# BSPDSchematic.net
KiCad netlist of a schematic drawn in Altium Designer
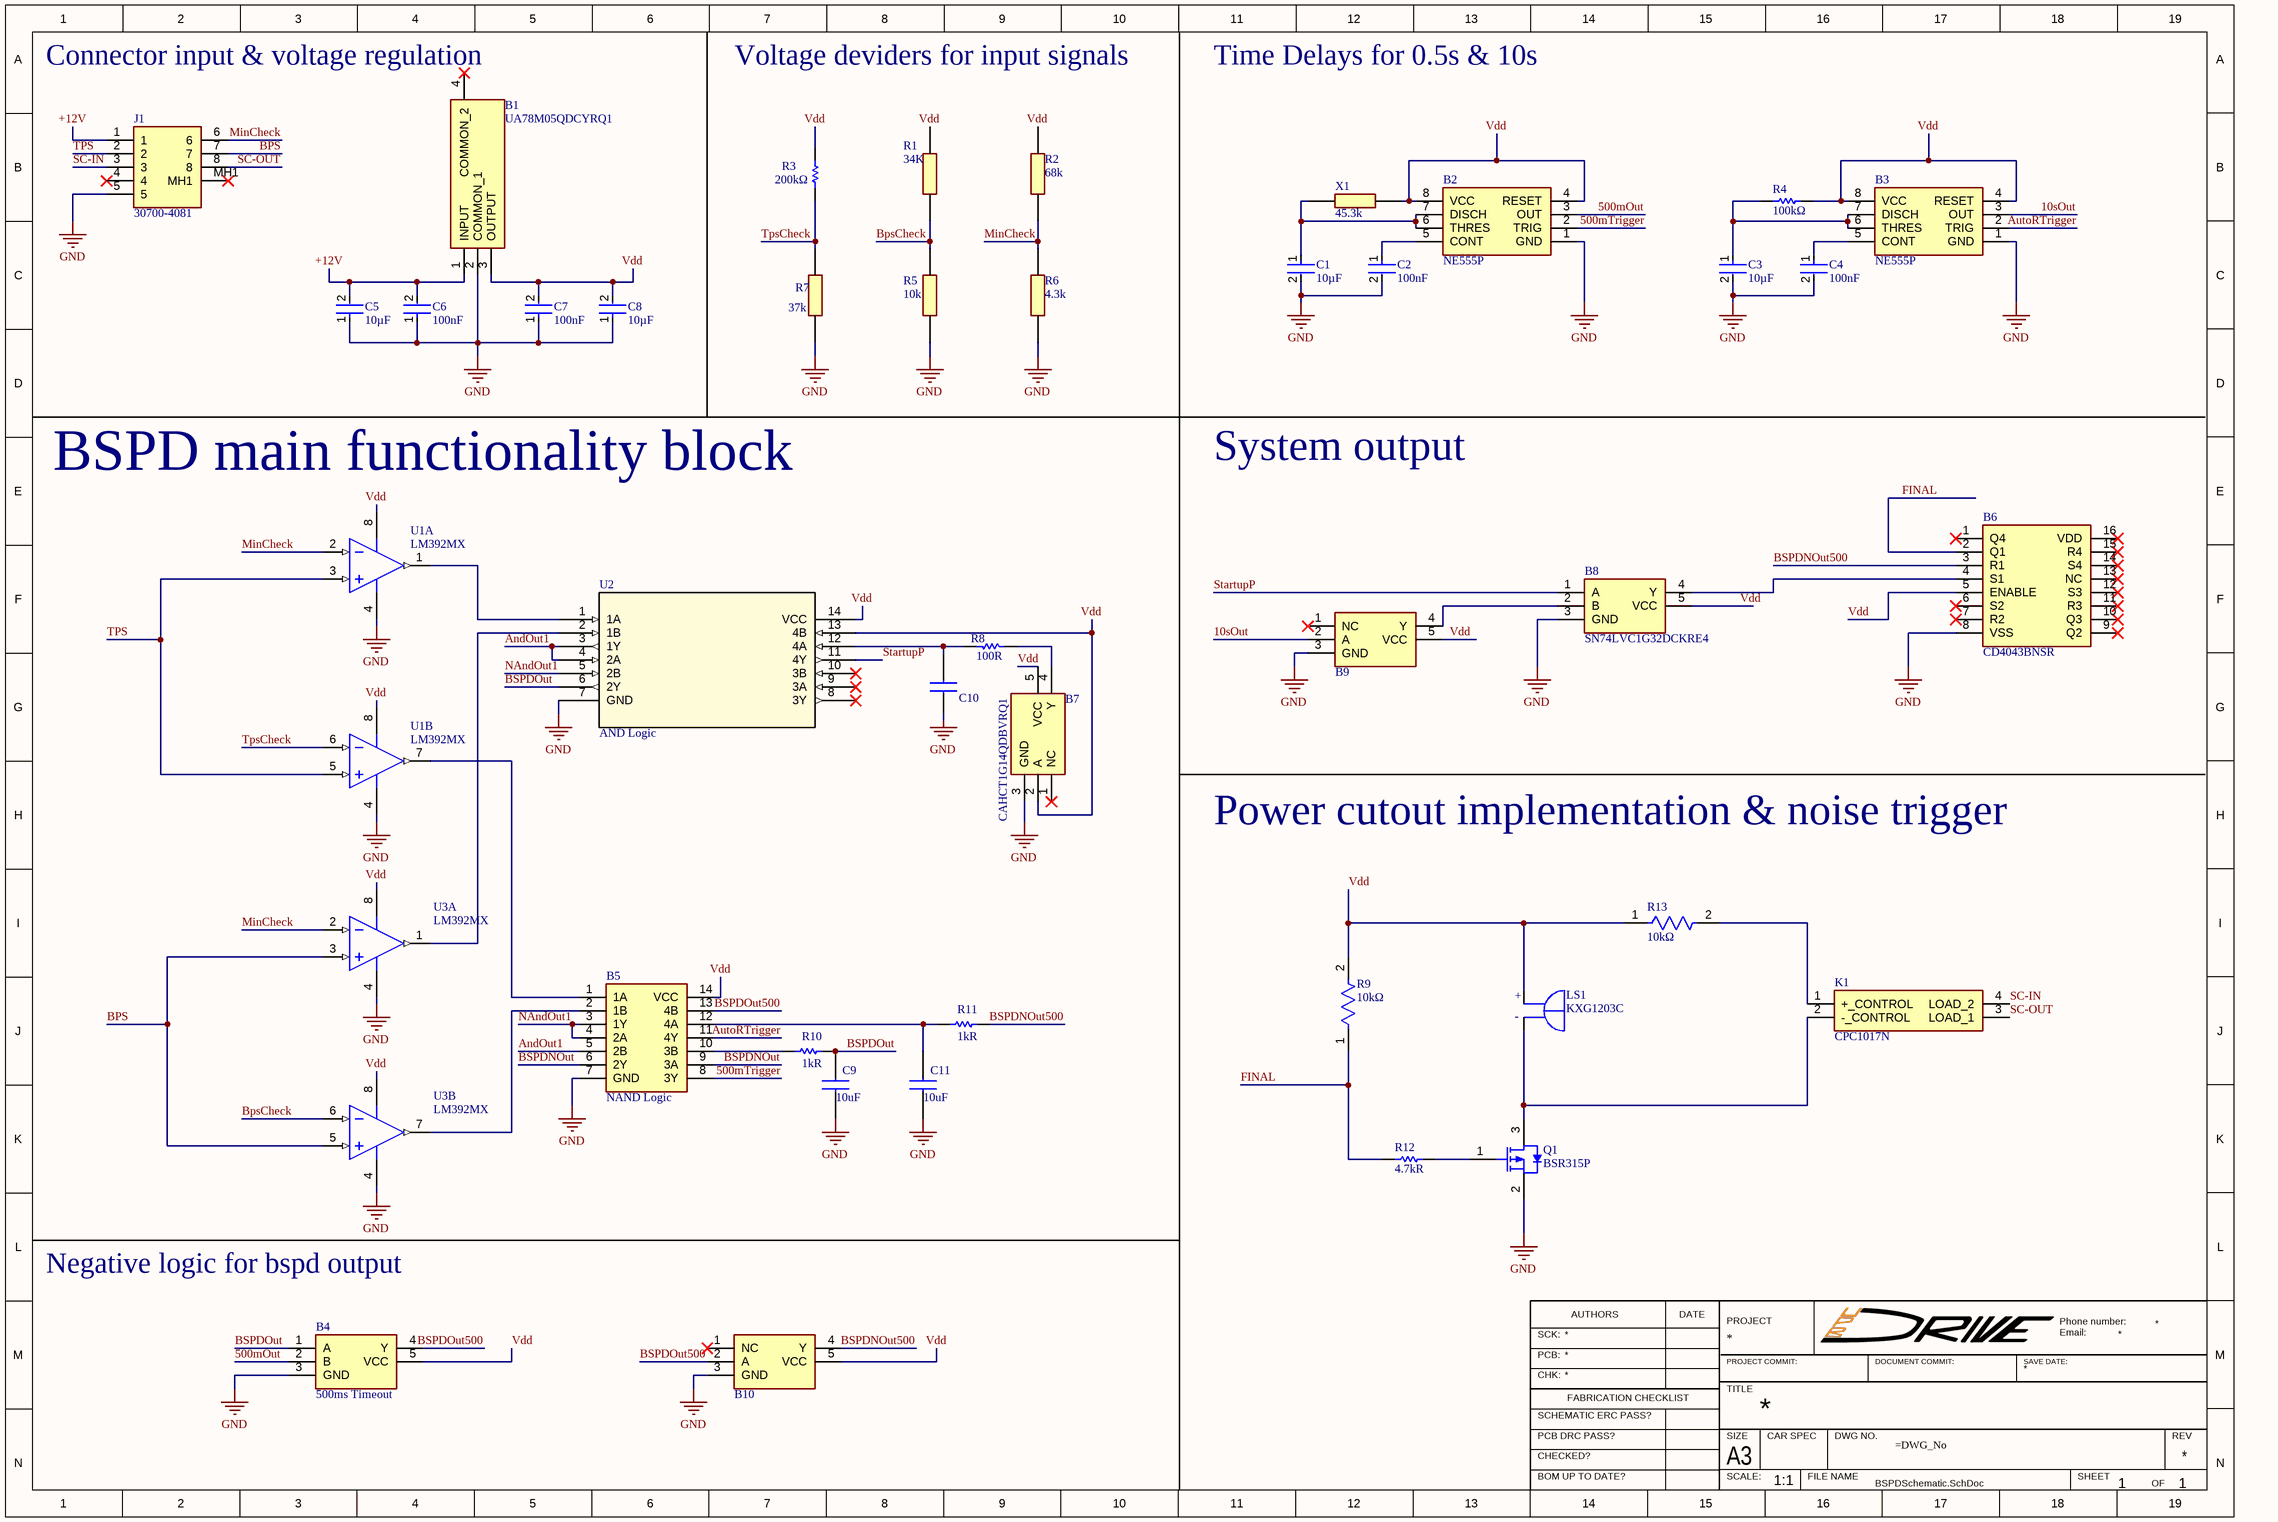
[diagram p0: BSPDSchematic.SchDoc]

(export (version "E")
  (design (tool "Eeschema 10.0.6"))
  (components
    (comp (ref "B1")
      (value "UA78M05QDCYRQ1")
      (footprint "SOT230P700X180-4N")
      (description "Standard Regulator Pos 5V 0.5A Automotive 4-Pin(3+Tab) SOT-223 T/R")
      (fields (field (name "MOUSER PART NUMBER") "595-UA78M05QDCYRQ1"))
      (libsource (lib "EMEA - Politehnica University of Bucharest - UPB Drive Formula Student Team") (part "UA78M05QDCYRQ1"))
    )
    (comp (ref "B2")
      (value "NE555P")
      (footprint "DIP794W53P254L959H508Q8N")
      (fields (field (name "MOUSER PART NUMBER") "595-NE555P"))
      (libsource (lib "EMEA - Politehnica University of Bucharest - UPB Drive Formula Student Team") (part "NE555P"))
    )
    (comp (ref "B3")
      (value "NE555P")
      (footprint "DIP794W53P254L959H508Q8N")
      (fields (field (name "MOUSER PART NUMBER") "595-NE555P"))
      (libsource (lib "EMEA - Politehnica University of Bucharest - UPB Drive Formula Student Team") (part "NE555P"))
    )
    (comp (ref "B4")
      (value "500ms Timeout")
      (footprint "SOT65P210X110-5N")
      (description "IC GATE XOR 1CH 2-INP SC70-5")
      (fields
        (field (name "MOUSER PART NUMBER") "595-SN74AHC1G86DCKE4")
        (field (name "MANUFACTURER_PART_NUMBER") "SN74AHC1G86DCKRE4")
      )
      (libsource (lib "EMEA - Politehnica University of Bucharest - UPB Drive Formula Student Team") (part "SN74AHC1G86DCKRE4"))
    )
    (comp (ref "B5")
      (value "NAND Logic")
      (footprint "SOIC127P780X200-14N")
      (description "Quadruple 2-Input Positive-NAND Gates")
      (fields
        (field (name "MANUFACTURER_PART_NUMBER") "SN74ACT00NSR")
        (field (name "MOUSER PART NUMBER") "595-SN74ACT00NSR")
      )
      (libsource (lib "EMEA - Politehnica University of Bucharest - UPB Drive Formula Student Team") (part "SN74ACT00NSR"))
    )
    (comp (ref "B6")
      (value "CD4043BNSR")
      (footprint "SOIC127P780X200-16N")
      (description "CMOS Quad NOR R/S Latch with 3-State Outputs")
      (fields (field (name "MOUSER PART NUMBER") "595-CD4043BNSR"))
      (libsource (lib "EMEA - Politehnica University of Bucharest - UPB Drive Formula Student Team") (part "CD4043BNSR"))
    )
    (comp (ref "B7")
      (value "CAHCT1G14QDBVRQ1")
      (footprint "SOT95P280X145-5N")
      (description "Automotive single 4.5V-to-5.5V inverter with Schmitt-trigger inputs")
      (fields (field (name "MOUSER PART NUMBER") "595-CAHCT1G14QDBVRQ1"))
      (libsource (lib "EMEA - Politehnica University of Bucharest - UPB Drive Formula Student Team") (part "CAHCT1G14QDBVRQ1"))
    )
    (comp (ref "B8")
      (value "SN74LVC1G32DCKRE4")
      (footprint "SOT65P210X110-5N")
      (description "OR Gate 1-Element 2-IN CMOS 5-Pin SC-70 T/R")
      (fields (field (name "MOUSER PART NUMBER") "595-74LVC1G32DCKRE4"))
      (libsource (lib "EMEA - Politehnica University of Bucharest - UPB Drive Formula Student Team") (part "SN74LVC1G32DCKRE4"))
    )
    (comp (ref "B9")
      (value "CAHCT1G14QDBVRQ1")
      (footprint "SOT95P280X145-5N")
      (description "Automotive single 4.5V-to-5.5V inverter with Schmitt-trigger inputs")
      (fields (field (name "MOUSER PART NUMBER") "595-CAHCT1G14QDBVRQ1"))
      (libsource (lib "EMEA - Politehnica University of Bucharest - UPB Drive Formula Student Team") (part "CAHCT1G14QDBVRQ1"))
    )
    (comp (ref "B10")
      (value "CAHCT1G14QDBVRQ1")
      (footprint "SOT95P280X145-5N")
      (description "Automotive single 4.5V-to-5.5V inverter with Schmitt-trigger inputs")
      (fields (field (name "MOUSER PART NUMBER") "595-CAHCT1G14QDBVRQ1"))
      (libsource (lib "EMEA - Politehnica University of Bucharest - UPB Drive Formula Student Team") (part "CAHCT1G14QDBVRQ1"))
    )
    (comp (ref "C1")
      (value "10µF")
      (footprint "FP-GRM21B-0_2-e0_2_0_7-MFG")
      (description "Multilayer Ceramic Capacitors MLCC - SMD/SMTSimulate & compare characteristics in SimSurfing")
      (fields (field (name "TOLERANCE") "20%") (field (name "Comment") "GRM21BR61H106ME43K"))
      (libsource (lib "EMEA - Politehnica University of Bucharest - UPB Drive Formula Student Team") (part "b4654b650e69147ec39a6b967a45e02"))
    )
    (comp (ref "C2")
      (value "100nF")
      (footprint "FP-CL31-IPC_C")
      (fields (field (name "Comment") "CL31B104KBCNNNL"))
      (libsource (lib "EMEA - Politehnica University of Bucharest - UPB Drive Formula Student Team") (part "b4654b650e69147ec39a6b967a45e02"))
    )
    (comp (ref "C3")
      (value "10µF")
      (footprint "FP-GRM21B-0_2-e0_2_0_7-MFG")
      (description "Multilayer Ceramic Capacitors MLCC - SMD/SMTSimulate & compare characteristics in SimSurfing")
      (fields (field (name "TOLERANCE") "20%") (field (name "Comment") "GRM21BR61H106ME43K"))
      (libsource (lib "EMEA - Politehnica University of Bucharest - UPB Drive Formula Student Team") (part "b4654b650e69147ec39a6b967a45e02"))
    )
    (comp (ref "C4")
      (value "100nF")
      (footprint "FP-CL31-IPC_C")
      (fields (field (name "Comment") "CL31B104KBCNNNL"))
      (libsource (lib "EMEA - Politehnica University of Bucharest - UPB Drive Formula Student Team") (part "b4654b650e69147ec39a6b967a45e02"))
    )
    (comp (ref "C5")
      (value "10µF")
      (footprint "FP-GRM21B-0_2-e0_2_0_7-MFG")
      (description "Multilayer Ceramic Capacitors MLCC - SMD/SMTSimulate & compare characteristics in SimSurfing")
      (fields (field (name "TOLERANCE") "20%") (field (name "Comment") "GRM21BR61H106ME43K"))
      (libsource (lib "EMEA - Politehnica University of Bucharest - UPB Drive Formula Student Team") (part "b4654b650e69147ec39a6b967a45e02"))
    )
    (comp (ref "C6")
      (value "100nF")
      (footprint "FP-0805-L_2_01_0_2-W_1_25-IPC_B")
      (fields (field (name "Comment") "08051C104K4Z2A"))
      (libsource (lib "EMEA - Politehnica University of Bucharest - UPB Drive Formula Student Team") (part "b4654b650e69147ec39a6b967a45e02"))
    )
    (comp (ref "C7")
      (value "100nF")
      (footprint "FP-0805-L_2_01_0_2-W_1_25-IPC_B")
      (fields (field (name "Comment") "08051C104K4Z2A"))
      (libsource (lib "EMEA - Politehnica University of Bucharest - UPB Drive Formula Student Team") (part "b4654b650e69147ec39a6b967a45e02"))
    )
    (comp (ref "C8")
      (value "10µF")
      (footprint "FP-GRM21B-0_2-e0_2_0_7-MFG")
      (description "Multilayer Ceramic Capacitors MLCC - SMD/SMTSimulate & compare characteristics in SimSurfing")
      (fields (field (name "TOLERANCE") "20%") (field (name "Comment") "GRM21BR61H106ME43K"))
      (libsource (lib "EMEA - Politehnica University of Bucharest - UPB Drive Formula Student Team") (part "b4654b650e69147ec39a6b967a45e02"))
    )
    (comp (ref "C9")
      (value "10uF")
      (footprint "GRM21BR60J226ME39L")
      (description "Multilayer Ceramic Capacitors MLCC - SMD/SMT 0805 10uF 20volts *Derate Voltage/Temp")
      (fields
        (field (name "MANUFACTURER_PART_NUMBER") "GRM21BC81D106KE51K")
        (field (name "MOUSER PART NUMBER") "81-GRM21BC81D106KE1K")
      )
      (libsource (lib "EMEA - Politehnica University of Bucharest - UPB Drive Formula Student Team") (part "GRM21BC81D106KE51K"))
    )
    (comp (ref "C10")
      (value "CL31A107MQHNNWE")
      (footprint "CAPC3216X180N")
      (fields (field (name "MOUSER PART NUMBER") "187-CL31A107MQHNNWE"))
      (libsource (lib "EMEA - Politehnica University of Bucharest - UPB Drive Formula Student Team") (part "CL31A107MQHNNWE"))
    )
    (comp (ref "C11")
      (value "10uF")
      (footprint "GRM21BR60J226ME39L")
      (description "Multilayer Ceramic Capacitors MLCC - SMD/SMT 0805 10uF 20volts *Derate Voltage/Temp")
      (fields
        (field (name "MANUFACTURER_PART_NUMBER") "GRM21BC81D106KE51K")
        (field (name "MOUSER PART NUMBER") "81-GRM21BC81D106KE1K")
      )
      (libsource (lib "EMEA - Politehnica University of Bucharest - UPB Drive Formula Student Team") (part "GRM21BC81D106KE51K"))
    )
    (comp (ref "J1")
      (value "30700-4081")
      (footprint "307004081")
      (description "Automotive Connectors HDAC64 DR VERT HDR 8 DR 8 CKT BLACK POL 2")
      (fields (field (name "MOUSER PART NUMBER") "538-30700-4081"))
      (libsource (lib "EMEA - Politehnica University of Bucharest - UPB Drive Formula Student Team") (part "30700-4081"))
    )
    (comp (ref "K1")
      (value "CPC1017N")
      (footprint "SOP254P610X206-4N")
      (description "Relay SSR 50mA 1.4V DC-IN 0.1A 60V 4-Pin SOP Tube")
      (fields (field (name "MOUSER PART NUMBER") "849-CPC1017N"))
      (libsource (lib "EMEA - Politehnica University of Bucharest - UPB Drive Formula Student Team") (part "CPC1017N"))
    )
    (comp (ref "LS1")
      (value "KXG1203C")
      (footprint "XDCR_KXG1203C")
      (libsource (lib "EMEA - Politehnica University of Bucharest - UPB Drive Formula Student Team") (part "KXG1203C"))
    )
    (comp (ref "Q1")
      (value "BSR315P")
      (footprint "INF-PG-SC59_M")
      (libsource (lib "EMEA - Politehnica University of Bucharest - UPB Drive Formula Student Team") (part "INF-PEMOS-GSD-3"))
    )
    (comp (ref "R1")
      (value "34K")
      (footprint "MCS04020C1003FE000")
      (description "Vishay Resistor Chip 0402")
      (fields (field (name "MANUFACTURER_PART_NUMBER") "MCS04020D3402BE000"))
      (libsource (lib "EMEA - Politehnica University of Bucharest - UPB Drive Formula Student Team") (part "MCS04020D3402BE000"))
    )
    (comp (ref "R2")
      (value "68k")
      (footprint "RESC1608X55N")
      (description "Thin Film Resistors - SMD MCT 0603-15 0.1% AT P5 68K")
      (fields
        (field (name "MANUFACTURER_PART_NUMBER") "MCT0603ME6802BP500")
        (field (name "MOUSER PART NUMBER") "594-MCT0603ME6802BP5")
      )
      (libsource (lib "EMEA - Politehnica University of Bucharest - UPB Drive Formula Student Team") (part "MCT0603ME6802BP500"))
    )
    (comp (ref "R3")
      (value "200kΩ")
      (footprint "RESC2013X60X35ML10T20")
      (description "Res Thick Film 0805 200K Ohm 1% 0.125W(1/8W) ±100ppm/C Molded SMD T/R")
      (fields (field (name "TOLERANCE") "1%") (field (name "Comment") "RC0805FR-13200KL"))
      (libsource (lib "EMEA - Politehnica University of Bucharest - UPB Drive Formula Student Team") (part "RES"))
    )
    (comp (ref "R4")
      (value "100kΩ")
      (footprint "RESC2013X60X30ML20T20")
      (description "Resistor Thick Film 0805 100K Ohm 1% 1/8W ±100ppm/°C SMD Punched Paper Tape and Reel")
      (fields (field (name "TOLERANCE") "1%") (field (name "Comment") "RK73H2ATTD1003F"))
      (libsource (lib "EMEA - Politehnica University of Bucharest - UPB Drive Formula Student Team") (part "RES"))
    )
    (comp (ref "R5")
      (value "10k")
      (footprint "RESC6332X70N")
      (description "10 +/-5% 1W Chip Resistor 2512 (6432 Metric) Automotive AEC-Q200 Thick Film")
      (fields
        (field (name "MOUSER PART NUMBER") "652-CR2512AJW-103ELF")
        (field (name "MANUFACTURER_PART_NUMBER") "CR2512AJW-103ELF")
      )
      (libsource (lib "EMEA - Politehnica University of Bucharest - UPB Drive Formula Student Team") (part "CR2512AJW-103ELF"))
    )
    (comp (ref "R6")
      (value "4.3k")
      (footprint "RESC1608X50N")
      (description "Thick Film Resistors - SMD 1/10watt 4.3Kohms 1%")
      (fields
        (field (name "MANUFACTURER_PART_NUMBER") "CRCW06034K30FKTA")
        (field (name "MOUSER PART NUMBER") "71-CRCW0603-4.3K")
      )
      (libsource (lib "EMEA - Politehnica University of Bucharest - UPB Drive Formula Student Team") (part "CRCW06034K30FKTA"))
    )
    (comp (ref "R7")
      (value "37k")
      (footprint "RESC1608X55N")
      (description "Lead (Pb)-Bearing High Stability Thin Film Chip Resistors")
      (fields
        (field (name "MOUSER PART NUMBER") "71-TNPW060337K0BEEA")
        (field (name "MANUFACTURER_PART_NUMBER") "TNPW060337K0BEEA")
      )
      (libsource (lib "EMEA - Politehnica University of Bucharest - UPB Drive Formula Student Team") (part "TNPW060337K0BEEA"))
    )
    (comp (ref "R8")
      (value "100R")
      (footprint "RESC3116X65X40ML10T20")
      (fields
        (field (name "TOLERANCE") "1%")
        (field (name "POWER") "250mW")
        (field (name "Comment") "RC1206FR-07100RL")
      )
      (libsource (lib "EMEA - Politehnica University of Bucharest - UPB Drive Formula Student Team") (part "RES-2"))
    )
    (comp (ref "R9")
      (value "10kΩ")
      (footprint "FP-RN731J-IPC_B")
      (description "RN 0603 SMD precision chip resistor 10K")
      (fields (field (name "TOLERANCE") "0.1%") (field (name "Comment") "RN73C1J10KB"))
      (libsource (lib "EMEA - Politehnica University of Bucharest - UPB Drive Formula Student Team") (part "1029c3af85768c4190bb7ad29bc67b5"))
    )
    (comp (ref "R10")
      (value "1kR")
      (footprint "RESC3216X60X45LL15T20")
      (fields
        (field (name "TOLERANCE") "1%")
        (field (name "POWER") "250mW")
        (field (name "Comment") "CRCW12061K00FKEA")
      )
      (libsource (lib "EMEA - Politehnica University of Bucharest - UPB Drive Formula Student Team") (part "RES-2"))
    )
    (comp (ref "R11")
      (value "1kR")
      (footprint "RESC3216X60X45LL15T20")
      (fields
        (field (name "TOLERANCE") "1%")
        (field (name "POWER") "250mW")
        (field (name "Comment") "CRCW12061K00FKEA")
      )
      (libsource (lib "EMEA - Politehnica University of Bucharest - UPB Drive Formula Student Team") (part "RES-2"))
    )
    (comp (ref "R12")
      (value "4.7kR")
      (footprint "RESC3216X60X45LL15T20")
      (fields
        (field (name "TOLERANCE") "1%")
        (field (name "POWER") "250mW")
        (field (name "Comment") "CRCW12064K70FKEA")
      )
      (libsource (lib "EMEA - Politehnica University of Bucharest - UPB Drive Formula Student Team") (part "RES-2"))
    )
    (comp (ref "R13")
      (value "10kΩ")
      (footprint "FP-RN731J-IPC_B")
      (description "RN 0603 SMD precision chip resistor 10K")
      (fields (field (name "TOLERANCE") "0.1%") (field (name "Comment") "RN73C1J10KB"))
      (libsource (lib "EMEA - Politehnica University of Bucharest - UPB Drive Formula Student Team") (part "1029c3af85768c4190bb7ad29bc67b5"))
    )
    (comp (ref "U1")
      (value "LM392MX")
      (footprint "D0008A_L")
      (description "lm392-N Low Power Operational Amplifier/Voltage Comparator")
      (libsource (lib "EMEA - Politehnica University of Bucharest - UPB Drive Formula Student Team") (part "AN-COMP-LM392-8"))
    )
    (comp (ref "U2")
      (value "AND Logic")
      (footprint "D14")
      (description "4-ch, 2-input, 2-V to 6-V 5.2 mA drive strength AND gate 14-SOIC -55 to 125")
      (fields
        (field (name "MANUFACTURER_PART_NUMBER") "CD74HC08M")
        (field (name "COPYRIGHT") "Copyright (C) 2025 Ultra Librarian. All rights reserved.")
      )
      (libsource (lib "EMEA - Politehnica University of Bucharest - UPB Drive Formula Student Team") (part "CD74HC08M"))
    )
    (comp (ref "U3")
      (value "LM392MX")
      (footprint "D0008A_L")
      (description "lm392-N Low Power Operational Amplifier/Voltage Comparator")
      (libsource (lib "EMEA - Politehnica University of Bucharest - UPB Drive Formula Student Team") (part "AN-COMP-LM392-8"))
    )
    (comp (ref "X1")
      (value "45.3k")
      (footprint "RESC3216X65N")
      (description "Thick Film Resistors - SMD 1206 45.3Kohm 1% High VoltageAEC-Q200")
      (fields
        (field (name "MANUFACTURER_PART_NUMBER") "KTR18EZPF4532")
        (field (name "MOUSER PART NUMBER") "755-KTR18EZPF4532")
      )
      (libsource (lib "EMEA - Politehnica University of Bucharest - UPB Drive Formula Student Team") (part "KTR18EZPF4532"))
    )
  )
  (nets
    (net (code "1") (name "/+12V") (class "Default")
      (node (ref "B1") (pin "1") (pinfunction "INPUT_1") (pintype "passive"))
      (node (ref "C5") (pin "2") (pinfunction "2_2") (pintype "passive"))
      (node (ref "C6") (pin "2") (pinfunction "2_2") (pintype "passive"))
      (node (ref "J1") (pin "1") (pinfunction "1_1") (pintype "passive"))
    )
    (net (code "2") (name "/10sOut") (class "Default")
      (node (ref "B3") (pin "3") (pinfunction "OUT_3") (pintype "passive"))
      (node (ref "B9") (pin "2") (pinfunction "A_2") (pintype "passive"))
    )
    (net (code "3") (name "/500mOut") (class "Default")
      (node (ref "B2") (pin "3") (pinfunction "OUT_3") (pintype "passive"))
      (node (ref "B4") (pin "2") (pinfunction "B_2") (pintype "passive"))
    )
    (net (code "4") (name "/500mTrigger") (class "Default")
      (node (ref "B2") (pin "2") (pinfunction "TRIG_2") (pintype "passive"))
      (node (ref "B5") (pin "8") (pinfunction "3Y_8") (pintype "passive"))
    )
    (net (code "5") (name "/AndOut1") (class "Default")
      (node (ref "B5") (pin "5") (pinfunction "2B_5") (pintype "passive"))
      (node (ref "U2") (pin "3") (pinfunction "1Y_3") (pintype "output"))
      (node (ref "U2") (pin "4") (pinfunction "2A_4") (pintype "input"))
    )
    (net (code "6") (name "/AutoRTrigger") (class "Default")
      (node (ref "B3") (pin "2") (pinfunction "TRIG_2") (pintype "passive"))
      (node (ref "B5") (pin "11") (pinfunction "4Y_11") (pintype "passive"))
    )
    (net (code "7") (name "/BPS") (class "Default")
      (node (ref "J1") (pin "7") (pinfunction "7_7") (pintype "passive"))
      (node (ref "U3") (pin "3") (pinfunction "INA+_3") (pintype "input"))
      (node (ref "U3") (pin "5") (pinfunction "INB+_5") (pintype "input"))
    )
    (net (code "8") (name "/BSPDNOut") (class "Default")
      (node (ref "B5") (pin "6") (pinfunction "2Y_6") (pintype "passive"))
      (node (ref "B5") (pin "9") (pinfunction "3A_9") (pintype "passive"))
    )
    (net (code "9") (name "/BSPDNOut500") (class "Default")
      (node (ref "B10") (pin "4") (pinfunction "Y_4") (pintype "passive"))
      (node (ref "B6") (pin "3") (pinfunction "R1_3") (pintype "passive"))
      (node (ref "R11") (pin "2") (pinfunction "2_2") (pintype "passive"))
    )
    (net (code "10") (name "/BSPDOut") (class "Default")
      (node (ref "B4") (pin "1") (pinfunction "A_1") (pintype "passive"))
      (node (ref "C9") (pin "2") (pinfunction "2_2") (pintype "passive"))
      (node (ref "R10") (pin "2") (pinfunction "2_2") (pintype "passive"))
      (node (ref "U2") (pin "6") (pinfunction "2Y_6") (pintype "output"))
    )
    (net (code "11") (name "/BSPDOut500") (class "Default")
      (node (ref "B10") (pin "2") (pinfunction "A_2") (pintype "passive"))
      (node (ref "B4") (pin "4") (pinfunction "Y_4") (pintype "passive"))
      (node (ref "B5") (pin "13") (pinfunction "4B_13") (pintype "passive"))
    )
    (net (code "12") (name "/BpsCheck") (class "Default")
      (node (ref "R1") (pin "1") (pinfunction "1_1") (pintype "passive"))
      (node (ref "R5") (pin "2") (pinfunction "2_2") (pintype "passive"))
      (node (ref "U3") (pin "6") (pinfunction "INB-_6") (pintype "input"))
    )
    (net (code "13") (name "/FINAL") (class "Default")
      (node (ref "B6") (pin "2") (pinfunction "Q1_2") (pintype "passive"))
      (node (ref "R12") (pin "1") (pinfunction "1_1") (pintype "passive"))
      (node (ref "R9") (pin "1") (pinfunction "1_1") (pintype "passive"))
    )
    (net (code "14") (name "/MinCheck") (class "Default")
      (node (ref "J1") (pin "6") (pinfunction "6_6") (pintype "passive"))
      (node (ref "R2") (pin "1") (pinfunction "1_1") (pintype "passive"))
      (node (ref "R6") (pin "2") (pinfunction "2_2") (pintype "passive"))
      (node (ref "U1") (pin "2") (pinfunction "INA-_2") (pintype "input"))
      (node (ref "U3") (pin "2") (pinfunction "INA-_2") (pintype "input"))
    )
    (net (code "15") (name "/NAndOut1") (class "Default")
      (node (ref "B5") (pin "3") (pinfunction "1Y_3") (pintype "passive"))
      (node (ref "B5") (pin "4") (pinfunction "2A_4") (pintype "passive"))
      (node (ref "U2") (pin "5") (pinfunction "2B_5") (pintype "input"))
    )
    (net (code "16") (name "/SC-IN") (class "Default")
      (node (ref "J1") (pin "3") (pinfunction "3_3") (pintype "passive"))
      (node (ref "K1") (pin "4") (pinfunction "LOAD_2_4") (pintype "passive"))
    )
    (net (code "17") (name "/SC-OUT") (class "Default")
      (node (ref "J1") (pin "8") (pinfunction "8_8") (pintype "passive"))
      (node (ref "K1") (pin "3") (pinfunction "LOAD_1_3") (pintype "passive"))
    )
    (net (code "18") (name "/StartupP") (class "Default")
      (node (ref "B8") (pin "1") (pinfunction "A_1") (pintype "passive"))
      (node (ref "U2") (pin "11") (pinfunction "4Y_11") (pintype "output"))
    )
    (net (code "19") (name "/TPS") (class "Default")
      (node (ref "J1") (pin "2") (pinfunction "2_2") (pintype "passive"))
      (node (ref "U1") (pin "3") (pinfunction "INA+_3") (pintype "input"))
      (node (ref "U1") (pin "5") (pinfunction "INB+_5") (pintype "input"))
    )
    (net (code "20") (name "/TpsCheck") (class "Default")
      (node (ref "R3") (pin "1") (pinfunction "1_1") (pintype "passive"))
      (node (ref "R7") (pin "2") (pinfunction "2_2") (pintype "passive"))
      (node (ref "U1") (pin "6") (pinfunction "INB-_6") (pintype "input"))
    )
    (net (code "21") (name "/Vdd") (class "Default")
      (node (ref "B1") (pin "3") (pinfunction "OUTPUT_3") (pintype "passive"))
      (node (ref "B10") (pin "5") (pinfunction "VCC_5") (pintype "passive"))
      (node (ref "B2") (pin "4") (pinfunction "RESET_4") (pintype "passive"))
      (node (ref "B2") (pin "8") (pinfunction "VCC_8") (pintype "passive"))
      (node (ref "B3") (pin "4") (pinfunction "RESET_4") (pintype "passive"))
      (node (ref "B3") (pin "8") (pinfunction "VCC_8") (pintype "passive"))
      (node (ref "B4") (pin "5") (pinfunction "VCC_5") (pintype "passive"))
      (node (ref "B5") (pin "14") (pinfunction "VCC_14") (pintype "passive"))
      (node (ref "B6") (pin "5") (pinfunction "ENABLE_5") (pintype "passive"))
      (node (ref "B7") (pin "2") (pinfunction "A_2") (pintype "passive"))
      (node (ref "B7") (pin "5") (pinfunction "VCC_5") (pintype "passive"))
      (node (ref "B8") (pin "5") (pinfunction "VCC_5") (pintype "passive"))
      (node (ref "B9") (pin "5") (pinfunction "VCC_5") (pintype "passive"))
      (node (ref "C7") (pin "2") (pinfunction "2_2") (pintype "passive"))
      (node (ref "C8") (pin "2") (pinfunction "2_2") (pintype "passive"))
      (node (ref "LS1") (pin "P") (pinfunction "POS_P") (pintype "passive"))
      (node (ref "R1") (pin "2") (pinfunction "2_2") (pintype "passive"))
      (node (ref "R13") (pin "1") (pinfunction "1_1") (pintype "passive"))
      (node (ref "R2") (pin "2") (pinfunction "2_2") (pintype "passive"))
      (node (ref "R3") (pin "2") (pinfunction "2_2") (pintype "passive"))
      (node (ref "R4") (pin "1") (pinfunction "1_1") (pintype "passive"))
      (node (ref "R9") (pin "2") (pinfunction "2_2") (pintype "passive"))
      (node (ref "U1") (pin "8") (pinfunction "V+_8") (pintype "power_in"))
      (node (ref "U2") (pin "13") (pinfunction "4B_13") (pintype "input"))
      (node (ref "U2") (pin "14") (pinfunction "VCC_14") (pintype "power_in"))
      (node (ref "U3") (pin "8") (pinfunction "V+_8") (pintype "power_in"))
      (node (ref "X1") (pin "1") (pinfunction "1_1") (pintype "passive"))
    )
    (net (code "22") (name "GND") (class "Default")
      (node (ref "B1") (pin "2") (pinfunction "COMMON_1_2") (pintype "passive"))
      (node (ref "B10") (pin "3") (pinfunction "GND_3") (pintype "passive"))
      (node (ref "B2") (pin "1") (pinfunction "GND_1") (pintype "passive"))
      (node (ref "B3") (pin "1") (pinfunction "GND_1") (pintype "passive"))
      (node (ref "B4") (pin "3") (pinfunction "GND_3") (pintype "passive"))
      (node (ref "B5") (pin "7") (pinfunction "GND_7") (pintype "passive"))
      (node (ref "B6") (pin "8") (pinfunction "VSS_8") (pintype "passive"))
      (node (ref "B7") (pin "3") (pinfunction "GND_3") (pintype "passive"))
      (node (ref "B8") (pin "3") (pinfunction "GND_3") (pintype "passive"))
      (node (ref "B9") (pin "3") (pinfunction "GND_3") (pintype "passive"))
      (node (ref "C1") (pin "2") (pinfunction "2_2") (pintype "passive"))
      (node (ref "C10") (pin "1") (pinfunction "1_1") (pintype "passive"))
      (node (ref "C11") (pin "1") (pinfunction "1_1") (pintype "passive"))
      (node (ref "C2") (pin "2") (pinfunction "2_2") (pintype "passive"))
      (node (ref "C3") (pin "2") (pinfunction "2_2") (pintype "passive"))
      (node (ref "C4") (pin "2") (pinfunction "2_2") (pintype "passive"))
      (node (ref "C5") (pin "1") (pinfunction "1_1") (pintype "passive"))
      (node (ref "C6") (pin "1") (pinfunction "1_1") (pintype "passive"))
      (node (ref "C7") (pin "1") (pinfunction "1_1") (pintype "passive"))
      (node (ref "C8") (pin "1") (pinfunction "1_1") (pintype "passive"))
      (node (ref "C9") (pin "1") (pinfunction "1_1") (pintype "passive"))
      (node (ref "J1") (pin "5") (pinfunction "5_5") (pintype "passive"))
      (node (ref "Q1") (pin "2") (pinfunction "SOURCE_2") (pintype "passive"))
      (node (ref "R5") (pin "1") (pinfunction "1_1") (pintype "passive"))
      (node (ref "R6") (pin "1") (pinfunction "1_1") (pintype "passive"))
      (node (ref "R7") (pin "1") (pinfunction "1_1") (pintype "passive"))
      (node (ref "U1") (pin "4") (pinfunction "GND_4") (pintype "power_in"))
      (node (ref "U2") (pin "7") (pinfunction "GND_7") (pintype "power_in"))
      (node (ref "U3") (pin "4") (pinfunction "GND_4") (pintype "power_in"))
    )
    (net (code "23") (name "Net-(B2-CONT)") (class "Default")
      (node (ref "B2") (pin "5") (pinfunction "CONT_5") (pintype "passive"))
      (node (ref "C2") (pin "1") (pinfunction "1_1") (pintype "passive"))
    )
    (net (code "24") (name "Net-(B2-DISCH)") (class "Default")
      (node (ref "B2") (pin "6") (pinfunction "THRES_6") (pintype "passive"))
      (node (ref "B2") (pin "7") (pinfunction "DISCH_7") (pintype "passive"))
      (node (ref "C1") (pin "1") (pinfunction "1_1") (pintype "passive"))
      (node (ref "X1") (pin "2") (pinfunction "2_2") (pintype "passive"))
    )
    (net (code "25") (name "Net-(B3-CONT)") (class "Default")
      (node (ref "B3") (pin "5") (pinfunction "CONT_5") (pintype "passive"))
      (node (ref "C4") (pin "1") (pinfunction "1_1") (pintype "passive"))
    )
    (net (code "26") (name "Net-(B3-DISCH)") (class "Default")
      (node (ref "B3") (pin "6") (pinfunction "THRES_6") (pintype "passive"))
      (node (ref "B3") (pin "7") (pinfunction "DISCH_7") (pintype "passive"))
      (node (ref "C3") (pin "1") (pinfunction "1_1") (pintype "passive"))
      (node (ref "R4") (pin "2") (pinfunction "2_2") (pintype "passive"))
    )
    (net (code "27") (name "Net-(B5-1A)") (class "Default")
      (node (ref "B5") (pin "1") (pinfunction "1A_1") (pintype "passive"))
      (node (ref "U1") (pin "7") (pinfunction "OUTB_7") (pintype "output"))
    )
    (net (code "28") (name "Net-(B5-1B)") (class "Default")
      (node (ref "B5") (pin "2") (pinfunction "1B_2") (pintype "passive"))
      (node (ref "U3") (pin "7") (pinfunction "OUTB_7") (pintype "output"))
    )
    (net (code "29") (name "Net-(B5-3B)") (class "Default")
      (node (ref "B5") (pin "10") (pinfunction "3B_10") (pintype "passive"))
      (node (ref "R10") (pin "1") (pinfunction "1_1") (pintype "passive"))
    )
    (net (code "30") (name "Net-(B5-4A)") (class "Default")
      (node (ref "B5") (pin "12") (pinfunction "4A_12") (pintype "passive"))
      (node (ref "C11") (pin "2") (pinfunction "2_2") (pintype "passive"))
      (node (ref "R11") (pin "1") (pinfunction "1_1") (pintype "passive"))
    )
    (net (code "31") (name "Net-(B6-S1)") (class "Default")
      (node (ref "B6") (pin "4") (pinfunction "S1_4") (pintype "passive"))
      (node (ref "B8") (pin "4") (pinfunction "Y_4") (pintype "passive"))
    )
    (net (code "32") (name "Net-(B7-Y)") (class "Default")
      (node (ref "B7") (pin "4") (pinfunction "Y_4") (pintype "passive"))
      (node (ref "R8") (pin "1") (pinfunction "1_1") (pintype "passive"))
    )
    (net (code "33") (name "Net-(B8-B)") (class "Default")
      (node (ref "B8") (pin "2") (pinfunction "B_2") (pintype "passive"))
      (node (ref "B9") (pin "4") (pinfunction "Y_4") (pintype "passive"))
    )
    (net (code "34") (name "Net-(K1-+_CONTROL)") (class "Default")
      (node (ref "K1") (pin "1") (pinfunction "+_CONTROL_1") (pintype "passive"))
      (node (ref "R13") (pin "2") (pinfunction "2_2") (pintype "passive"))
    )
    (net (code "35") (name "Net-(K1--_CONTROL)") (class "Default")
      (node (ref "K1") (pin "2") (pinfunction "-_CONTROL_2") (pintype "passive"))
      (node (ref "LS1") (pin "N") (pinfunction "NEG_N") (pintype "passive"))
      (node (ref "Q1") (pin "3") (pinfunction "DRAIN_3") (pintype "passive"))
    )
    (net (code "36") (name "Net-(Q1-GATE)") (class "Default")
      (node (ref "Q1") (pin "1") (pinfunction "GATE_1") (pintype "passive"))
      (node (ref "R12") (pin "2") (pinfunction "2_2") (pintype "passive"))
    )
    (net (code "37") (name "Net-(U1A-OUTA)") (class "Default")
      (node (ref "U1") (pin "1") (pinfunction "OUTA_1") (pintype "output"))
      (node (ref "U2") (pin "1") (pinfunction "1A_1") (pintype "input"))
    )
    (net (code "38") (name "Net-(U2-1B)") (class "Default")
      (node (ref "U2") (pin "2") (pinfunction "1B_2") (pintype "input"))
      (node (ref "U3") (pin "1") (pinfunction "OUTA_1") (pintype "output"))
    )
    (net (code "39") (name "Net-(U2-4A)") (class "Default")
      (node (ref "C10") (pin "2") (pinfunction "2_2") (pintype "passive"))
      (node (ref "R8") (pin "2") (pinfunction "2_2") (pintype "passive"))
      (node (ref "U2") (pin "12") (pinfunction "4A_12") (pintype "input"))
    )
    (net (code "40") (name "unconnected-(B1-COMMON_2-Pad4)") (class "Default")
      (node (ref "B1") (pin "4") (pinfunction "COMMON_2_4") (pintype "passive+no_connect"))
    )
    (net (code "41") (name "unconnected-(B6-NC-Pad13)") (class "Default")
      (node (ref "B6") (pin "13") (pinfunction "NC_13") (pintype "passive+no_connect"))
    )
    (net (code "42") (name "unconnected-(B6-Q2-Pad9)") (class "Default")
      (node (ref "B6") (pin "9") (pinfunction "Q2_9") (pintype "passive+no_connect"))
    )
    (net (code "43") (name "unconnected-(B6-Q3-Pad10)") (class "Default")
      (node (ref "B6") (pin "10") (pinfunction "Q3_10") (pintype "passive+no_connect"))
    )
    (net (code "44") (name "unconnected-(B6-Q4-Pad1)") (class "Default")
      (node (ref "B6") (pin "1") (pinfunction "Q4_1") (pintype "passive+no_connect"))
    )
    (net (code "45") (name "unconnected-(B6-R2-Pad7)") (class "Default")
      (node (ref "B6") (pin "7") (pinfunction "R2_7") (pintype "passive+no_connect"))
    )
    (net (code "46") (name "unconnected-(B6-R3-Pad11)") (class "Default")
      (node (ref "B6") (pin "11") (pinfunction "R3_11") (pintype "passive+no_connect"))
    )
    (net (code "47") (name "unconnected-(B6-R4-Pad15)") (class "Default")
      (node (ref "B6") (pin "15") (pinfunction "R4_15") (pintype "passive+no_connect"))
    )
    (net (code "48") (name "unconnected-(B6-S2-Pad6)") (class "Default")
      (node (ref "B6") (pin "6") (pinfunction "S2_6") (pintype "passive+no_connect"))
    )
    (net (code "49") (name "unconnected-(B6-S3-Pad12)") (class "Default")
      (node (ref "B6") (pin "12") (pinfunction "S3_12") (pintype "passive+no_connect"))
    )
    (net (code "50") (name "unconnected-(B6-S4-Pad14)") (class "Default")
      (node (ref "B6") (pin "14") (pinfunction "S4_14") (pintype "passive+no_connect"))
    )
    (net (code "51") (name "unconnected-(B6-VDD-Pad16)") (class "Default")
      (node (ref "B6") (pin "16") (pinfunction "VDD_16") (pintype "passive+no_connect"))
    )
    (net (code "52") (name "unconnected-(B7-NC-Pad1)") (class "Default")
      (node (ref "B7") (pin "1") (pinfunction "NC_1") (pintype "passive+no_connect"))
    )
    (net (code "53") (name "unconnected-(B9-NC-Pad1)") (class "Default")
      (node (ref "B9") (pin "1") (pinfunction "NC_1") (pintype "passive+no_connect"))
    )
    (net (code "54") (name "unconnected-(B10-NC-Pad1)") (class "Default")
      (node (ref "B10") (pin "1") (pinfunction "NC_1") (pintype "passive+no_connect"))
    )
    (net (code "55") (name "unconnected-(J1-Pad4)") (class "Default")
      (node (ref "J1") (pin "4") (pinfunction "4_4") (pintype "passive+no_connect"))
    )
    (net (code "56") (name "unconnected-(J1-PadMH1)") (class "Default")
      (node (ref "J1") (pin "MH1") (pinfunction "MH1_MH1") (pintype "passive+no_connect"))
    )
    (net (code "57") (name "unconnected-(U2-3A-Pad9)") (class "Default")
      (node (ref "U2") (pin "9") (pinfunction "3A_9") (pintype "input+no_connect"))
    )
    (net (code "58") (name "unconnected-(U2-3B-Pad10)") (class "Default")
      (node (ref "U2") (pin "10") (pinfunction "3B_10") (pintype "input+no_connect"))
    )
    (net (code "59") (name "unconnected-(U2-3Y-Pad8)") (class "Default")
      (node (ref "U2") (pin "8") (pinfunction "3Y_8") (pintype "output+no_connect"))
    )
  )
)
